# AOBoard.net
KiCad netlist of a schematic drawn in Altium Designer
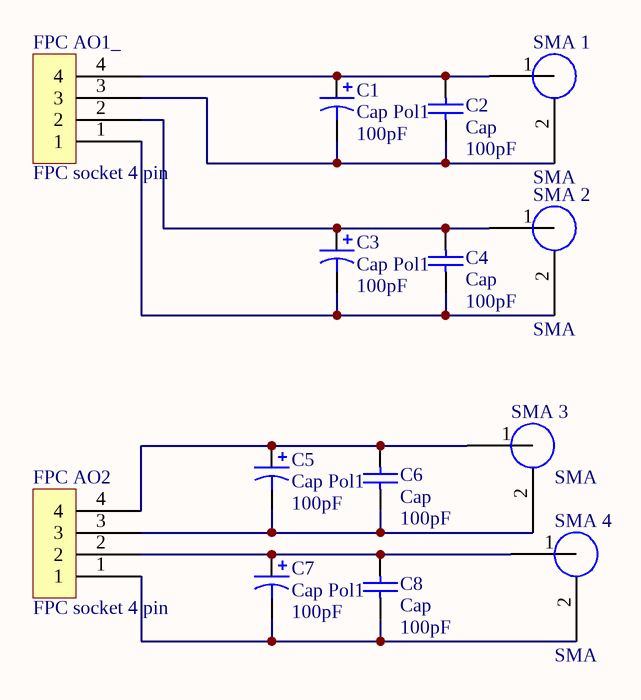
[diagram p0: AOBoard.SchDoc]

(export (version "E")
  (design (tool "Eeschema 10.0.6"))
  (components
    (comp (ref "C1")
      (value "Cap Pol1")
      (footprint "RB7.6-15")
      (description "Polarized Capacitor (Radial)")
      (fields (field (name "ALTIUM_VALUE") "100pF") (field (name "PUBLISHER") "Altium Limited"))
      (libsource (lib "Miscellaneous Devices") (part "Cap Pol1"))
    )
    (comp (ref "C2")
      (value "Cap")
      (footprint "RAD-0.3")
      (description "Capacitor")
      (fields (field (name "ALTIUM_VALUE") "100pF") (field (name "PUBLISHER") "Altium Limited"))
      (libsource (lib "Miscellaneous Devices") (part "Cap"))
    )
    (comp (ref "C3")
      (value "Cap Pol1")
      (footprint "RB7.6-15")
      (description "Polarized Capacitor (Radial)")
      (fields (field (name "ALTIUM_VALUE") "100pF") (field (name "PUBLISHER") "Altium Limited"))
      (libsource (lib "Miscellaneous Devices") (part "Cap Pol1"))
    )
    (comp (ref "C4")
      (value "Cap")
      (footprint "RAD-0.3")
      (description "Capacitor")
      (fields (field (name "ALTIUM_VALUE") "100pF") (field (name "PUBLISHER") "Altium Limited"))
      (libsource (lib "Miscellaneous Devices") (part "Cap"))
    )
    (comp (ref "C5")
      (value "Cap Pol1")
      (footprint "RB7.6-15")
      (description "Polarized Capacitor (Radial)")
      (fields (field (name "ALTIUM_VALUE") "100pF") (field (name "PUBLISHER") "Altium Limited"))
      (libsource (lib "Miscellaneous Devices") (part "Cap Pol1"))
    )
    (comp (ref "C6")
      (value "Cap")
      (footprint "RAD-0.3")
      (description "Capacitor")
      (fields (field (name "ALTIUM_VALUE") "100pF") (field (name "PUBLISHER") "Altium Limited"))
      (libsource (lib "Miscellaneous Devices") (part "Cap"))
    )
    (comp (ref "C7")
      (value "Cap Pol1")
      (footprint "RB7.6-15")
      (description "Polarized Capacitor (Radial)")
      (fields (field (name "ALTIUM_VALUE") "100pF") (field (name "PUBLISHER") "Altium Limited"))
      (libsource (lib "Miscellaneous Devices") (part "Cap Pol1"))
    )
    (comp (ref "C8")
      (value "Cap")
      (footprint "RAD-0.3")
      (description "Capacitor")
      (fields (field (name "ALTIUM_VALUE") "100pF") (field (name "PUBLISHER") "Altium Limited"))
      (libsource (lib "Miscellaneous Devices") (part "Cap"))
    )
    (comp (ref "FPC AO1_")
      (value "FPC socket 4 pin")
      (footprint "FPC 4Pin")
      (libsource (lib "Libaray") (part "FPC socket 4 pin"))
    )
    (comp (ref "FPC AO2")
      (value "FPC socket 4 pin")
      (footprint "FPC 4Pin")
      (libsource (lib "Libaray") (part "FPC socket 4 pin"))
    )
    (comp (ref "SMA 1") (value "SMA") (footprint "SMA") (libsource (lib "Libaray") (part "SMA")))
    (comp (ref "SMA 2") (value "SMA") (footprint "SMA") (libsource (lib "Libaray") (part "SMA")))
    (comp (ref "SMA 3") (value "SMA") (footprint "SMA") (libsource (lib "Libaray") (part "SMA")))
    (comp (ref "SMA 4") (value "SMA") (footprint "SMA") (libsource (lib "Libaray") (part "SMA")))
  )
  (nets
    (net (code "1") (name "Net-(SMA 1-Core)") (class "Default")
      (node (ref "C1") (pin "1") (pinfunction "1_1") (pintype "passive"))
      (node (ref "C2") (pin "2") (pinfunction "2_2") (pintype "passive"))
      (node (ref "FPC AO1_") (pin "4") (pinfunction "4_4") (pintype "passive"))
      (node (ref "SMA 1") (pin "1") (pinfunction "Core_1") (pintype "passive"))
    )
    (net (code "2") (name "Net-(SMA 1-Ground)") (class "Default")
      (node (ref "C1") (pin "2") (pinfunction "2_2") (pintype "passive"))
      (node (ref "C2") (pin "1") (pinfunction "1_1") (pintype "passive"))
      (node (ref "FPC AO1_") (pin "3") (pinfunction "3_3") (pintype "passive"))
      (node (ref "SMA 1") (pin "2") (pinfunction "Ground_2") (pintype "passive"))
    )
    (net (code "3") (name "Net-(SMA 2-Core)") (class "Default")
      (node (ref "C3") (pin "1") (pinfunction "1_1") (pintype "passive"))
      (node (ref "C4") (pin "2") (pinfunction "2_2") (pintype "passive"))
      (node (ref "FPC AO1_") (pin "2") (pinfunction "2_2") (pintype "passive"))
      (node (ref "SMA 2") (pin "1") (pinfunction "Core_1") (pintype "passive"))
    )
    (net (code "4") (name "Net-(SMA 2-Ground)") (class "Default")
      (node (ref "C3") (pin "2") (pinfunction "2_2") (pintype "passive"))
      (node (ref "C4") (pin "1") (pinfunction "1_1") (pintype "passive"))
      (node (ref "FPC AO1_") (pin "1") (pinfunction "1_1") (pintype "passive"))
      (node (ref "SMA 2") (pin "2") (pinfunction "Ground_2") (pintype "passive"))
    )
    (net (code "5") (name "Net-(SMA 3-Core)") (class "Default")
      (node (ref "C5") (pin "1") (pinfunction "1_1") (pintype "passive"))
      (node (ref "C6") (pin "2") (pinfunction "2_2") (pintype "passive"))
      (node (ref "FPC AO2") (pin "4") (pinfunction "4_4") (pintype "passive"))
      (node (ref "SMA 3") (pin "1") (pinfunction "Core_1") (pintype "passive"))
    )
    (net (code "6") (name "Net-(SMA 3-Ground)") (class "Default")
      (node (ref "C5") (pin "2") (pinfunction "2_2") (pintype "passive"))
      (node (ref "C6") (pin "1") (pinfunction "1_1") (pintype "passive"))
      (node (ref "FPC AO2") (pin "3") (pinfunction "3_3") (pintype "passive"))
      (node (ref "SMA 3") (pin "2") (pinfunction "Ground_2") (pintype "passive"))
    )
    (net (code "7") (name "Net-(SMA 4-Core)") (class "Default")
      (node (ref "C7") (pin "1") (pinfunction "1_1") (pintype "passive"))
      (node (ref "C8") (pin "2") (pinfunction "2_2") (pintype "passive"))
      (node (ref "FPC AO2") (pin "2") (pinfunction "2_2") (pintype "passive"))
      (node (ref "SMA 4") (pin "1") (pinfunction "Core_1") (pintype "passive"))
    )
    (net (code "8") (name "Net-(SMA 4-Ground)") (class "Default")
      (node (ref "C7") (pin "2") (pinfunction "2_2") (pintype "passive"))
      (node (ref "C8") (pin "1") (pinfunction "1_1") (pintype "passive"))
      (node (ref "FPC AO2") (pin "1") (pinfunction "1_1") (pintype "passive"))
      (node (ref "SMA 4") (pin "2") (pinfunction "Ground_2") (pintype "passive"))
    )
  )
)
